# 05__eda__esp32_-__2024-09-18.net
KiCad netlist of a schematic drawn in EasyEDA Pro
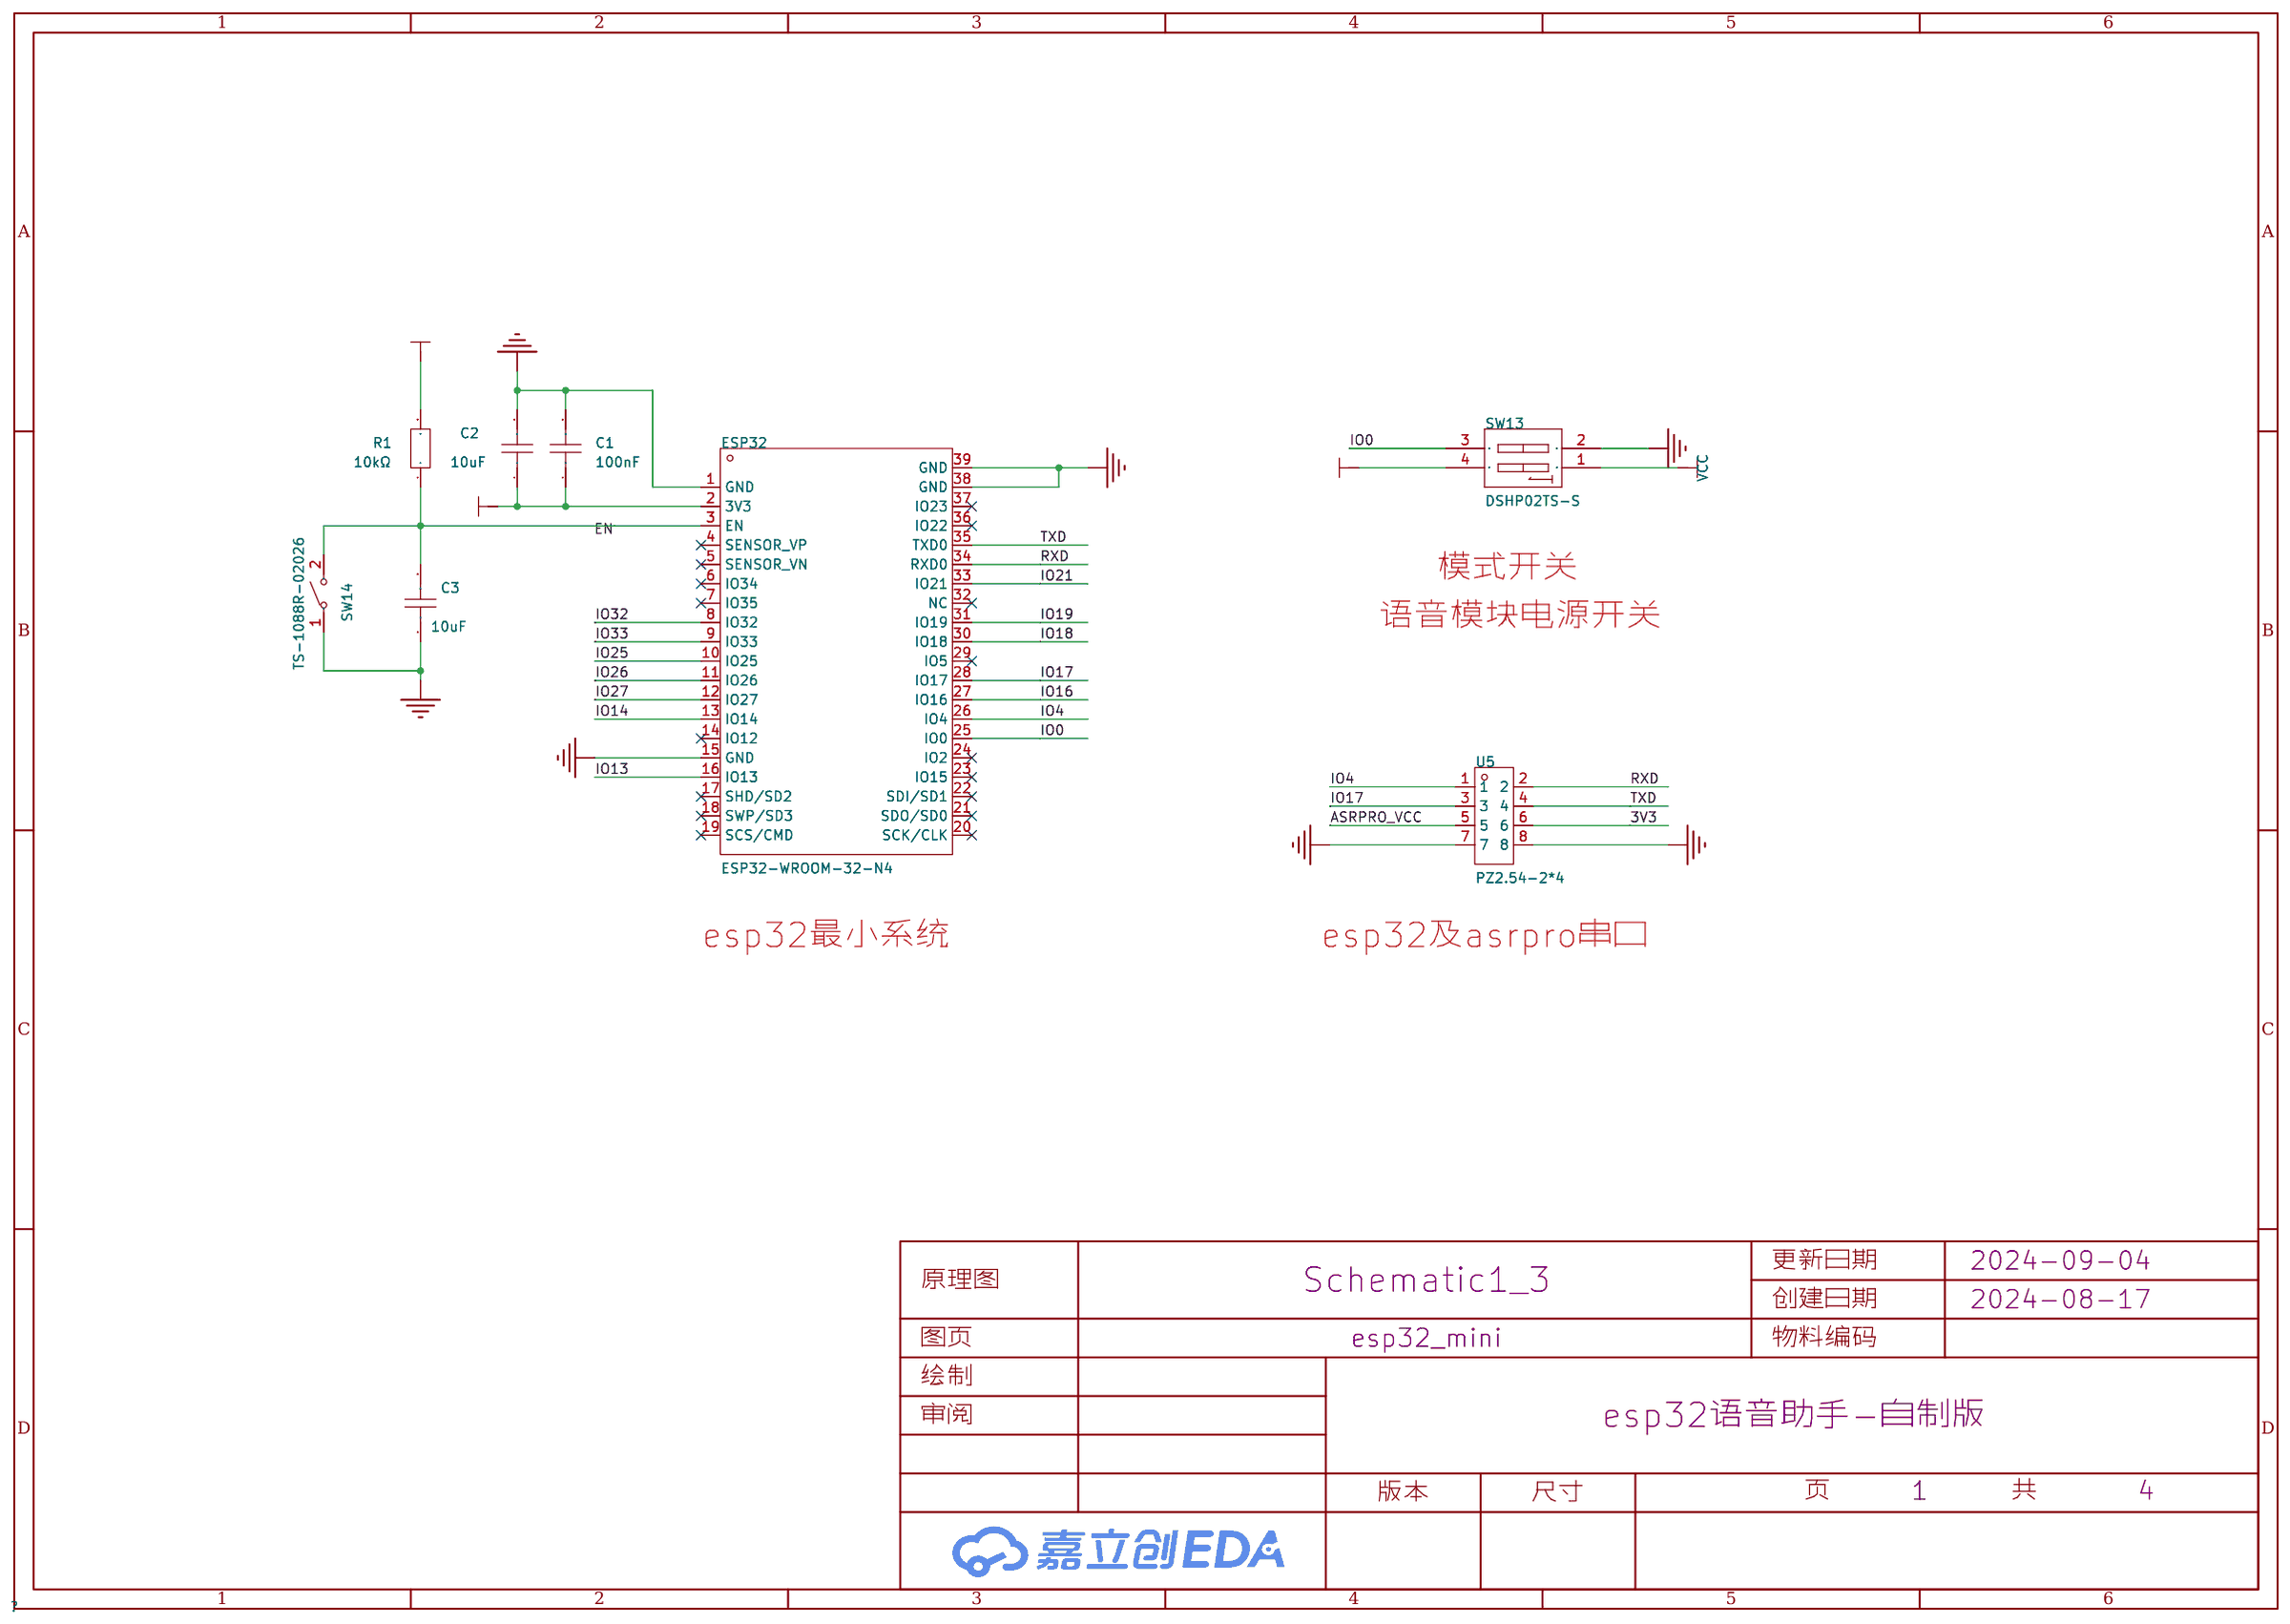
[diagram p0: esp32_mini]
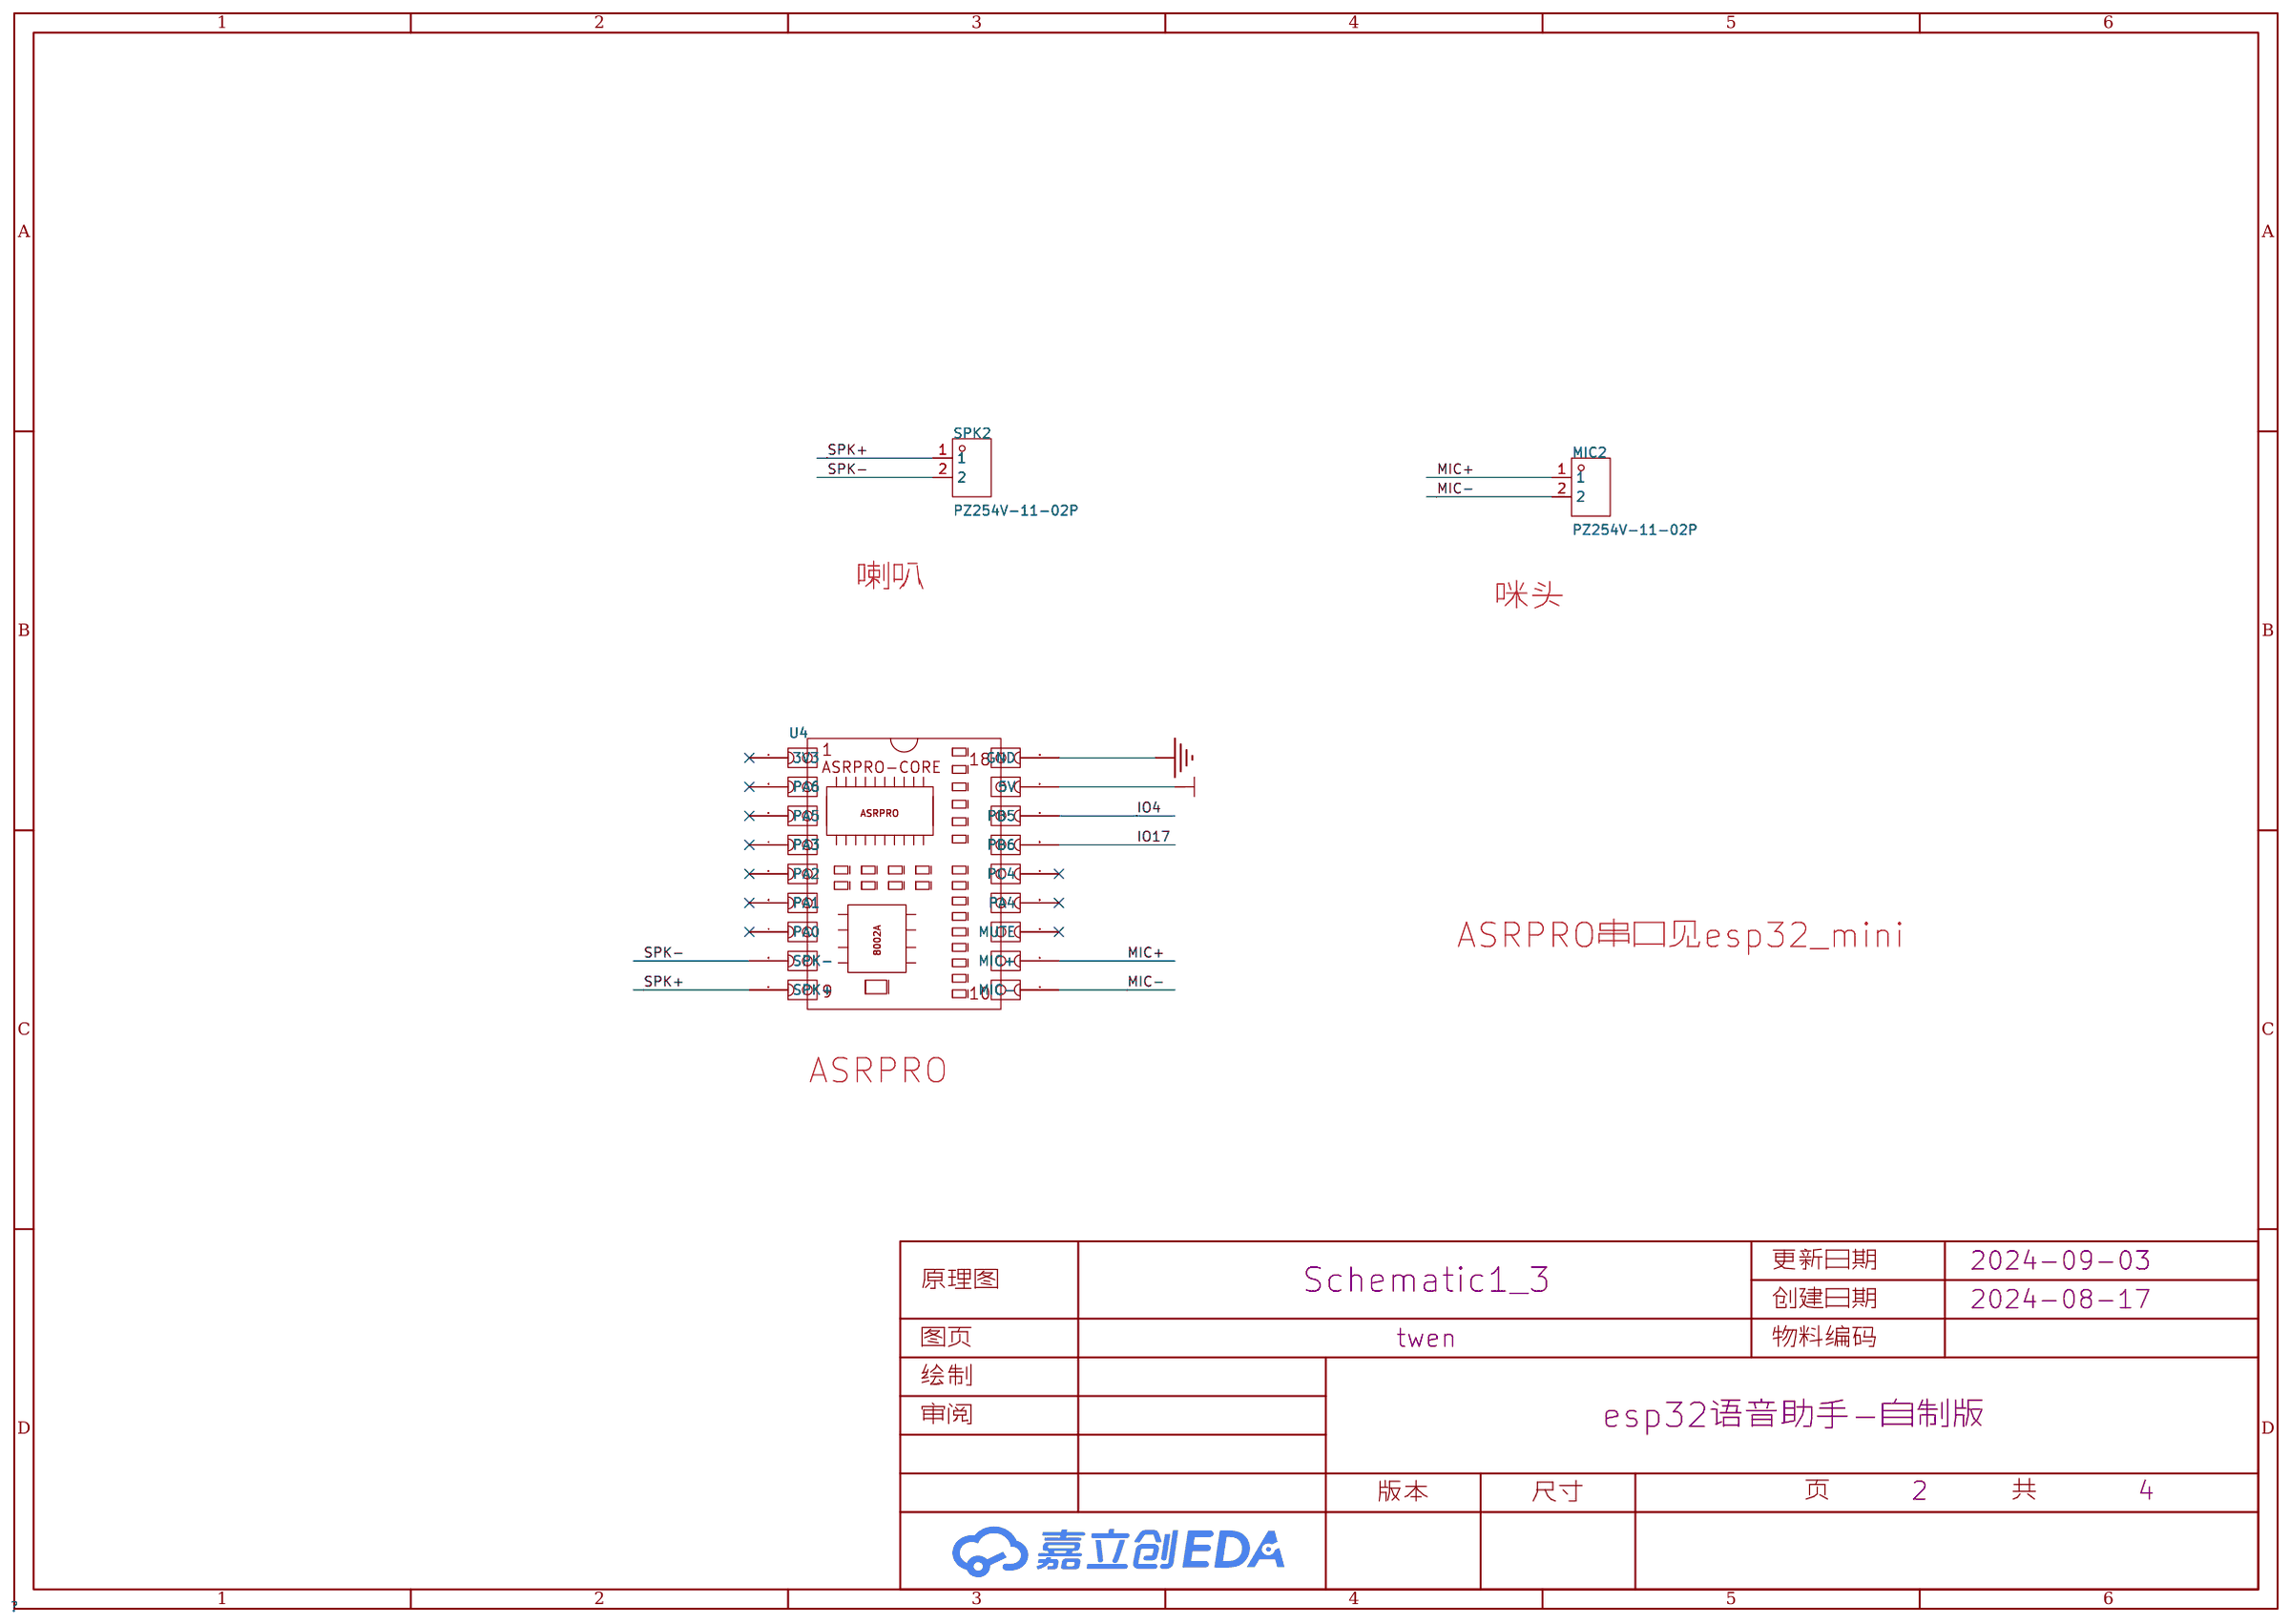
[diagram p1: twen]
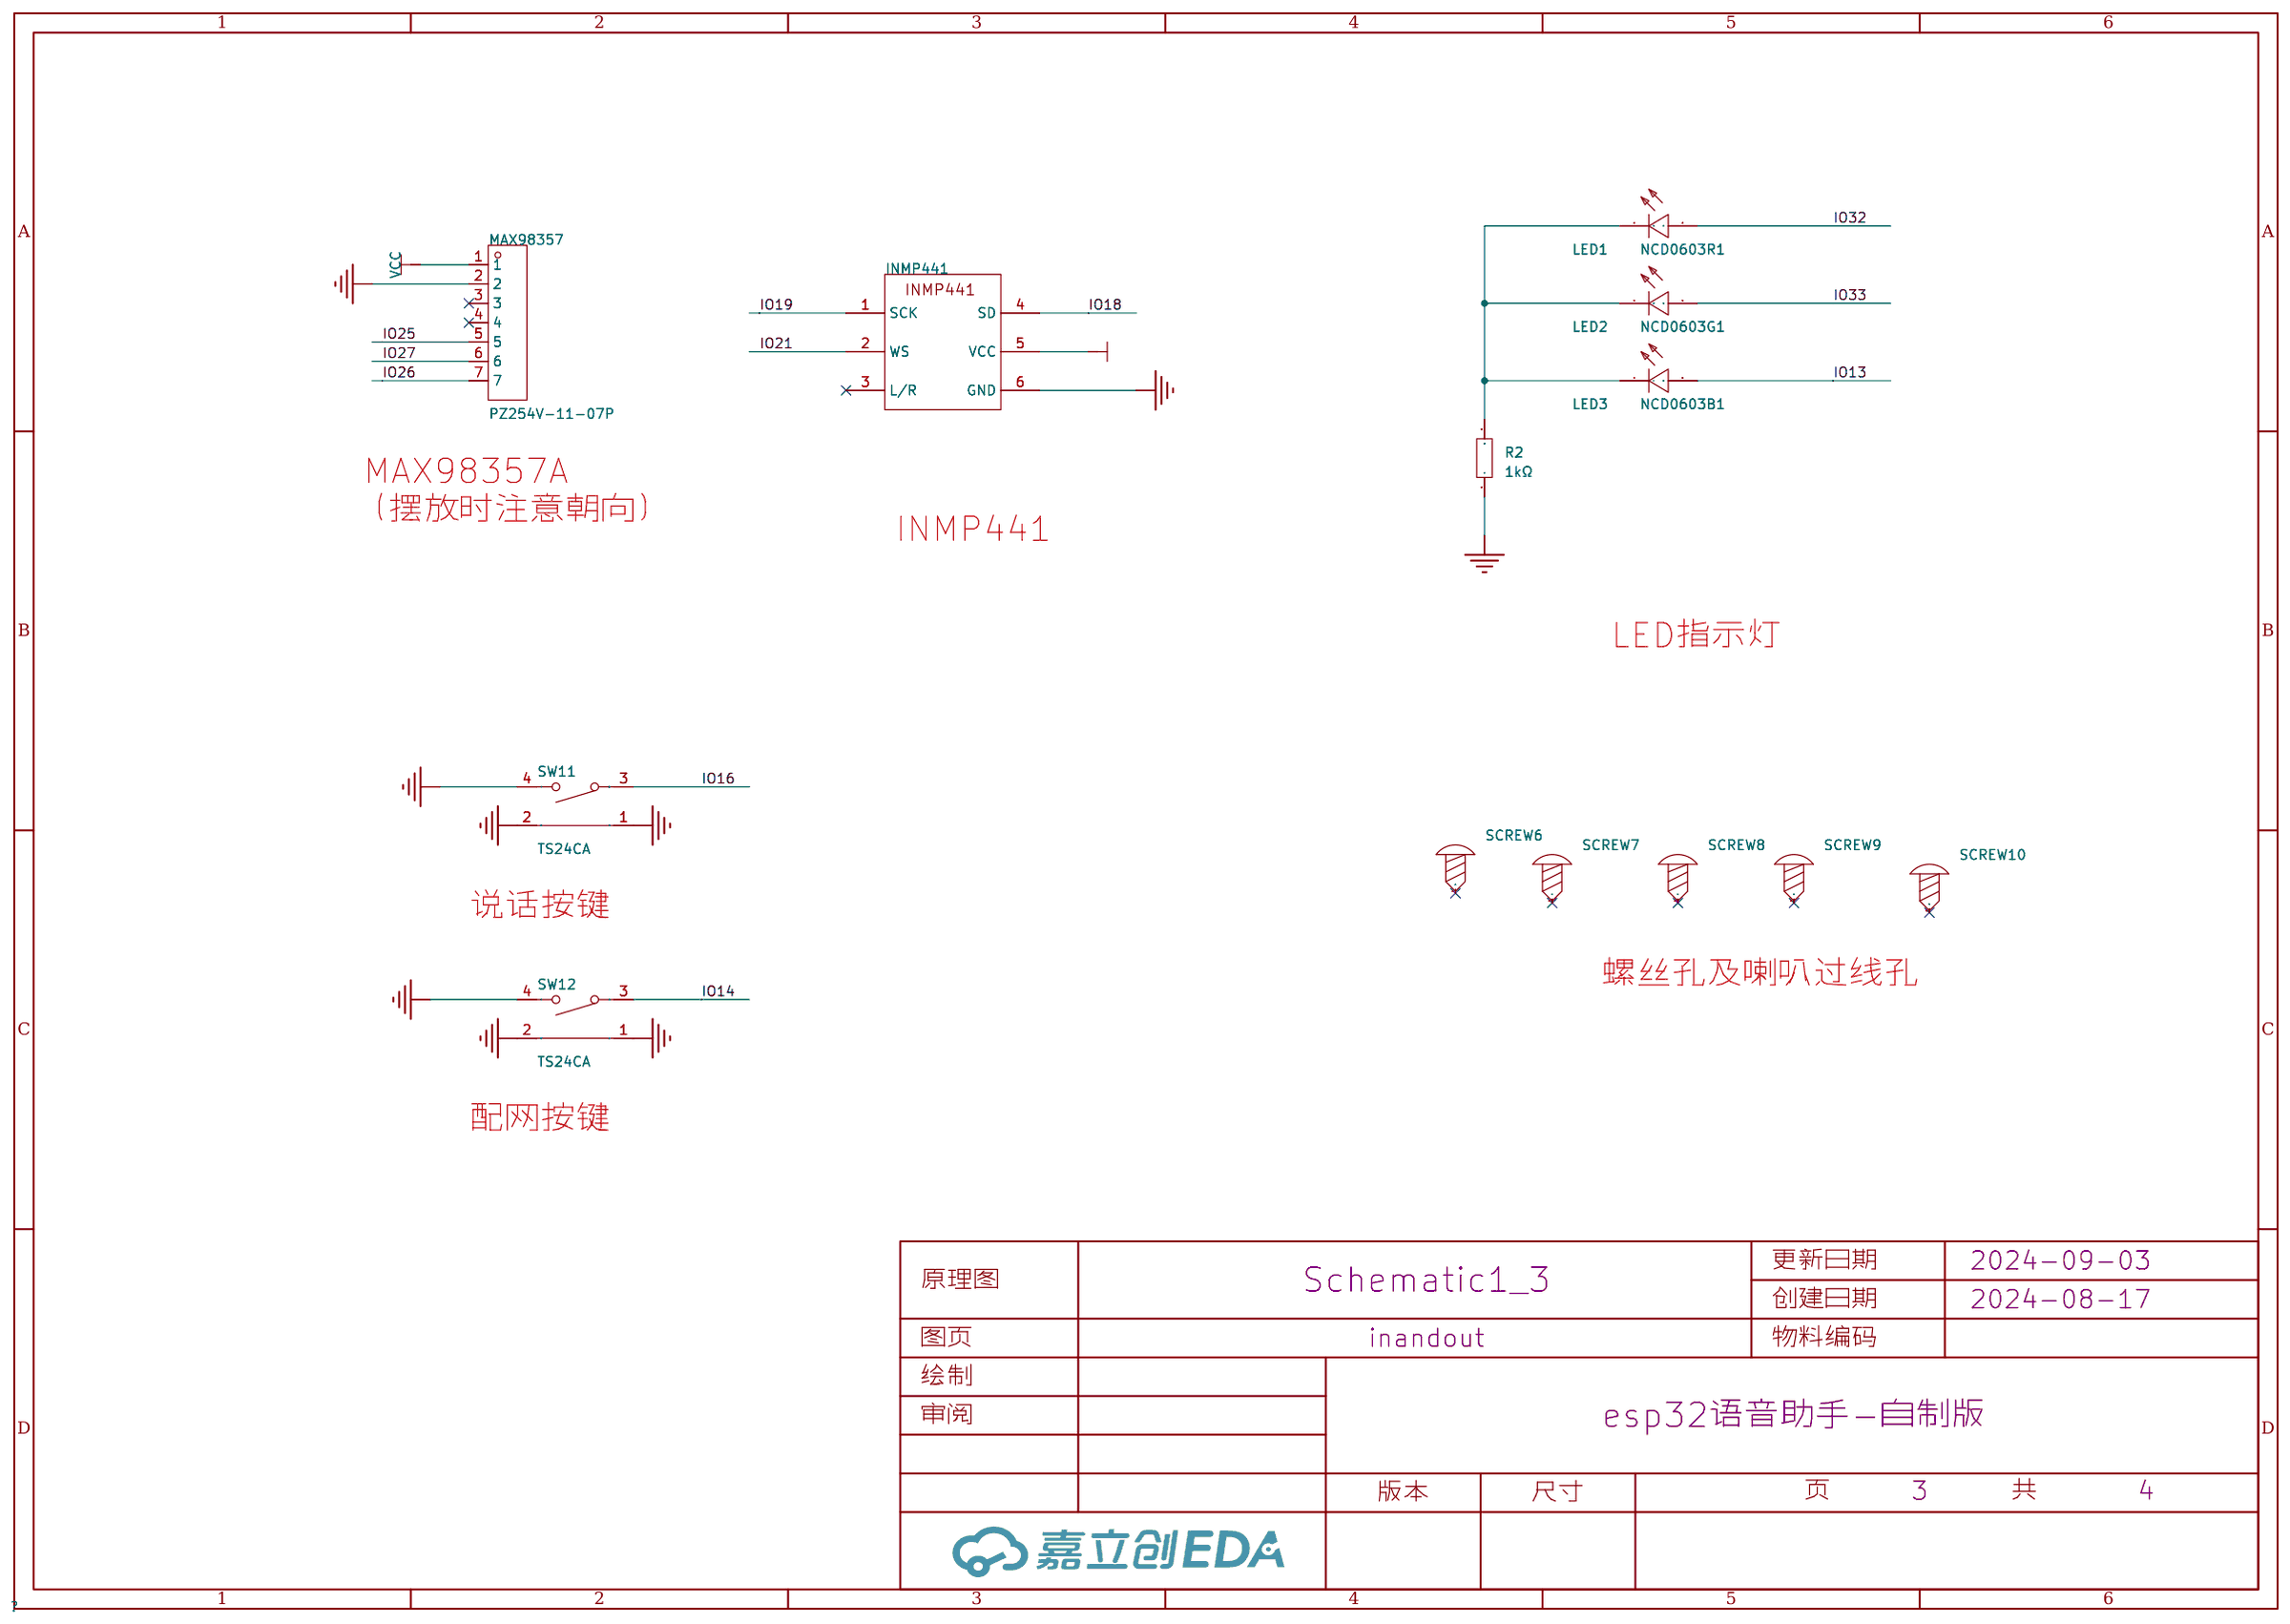
[diagram p2: inandout]
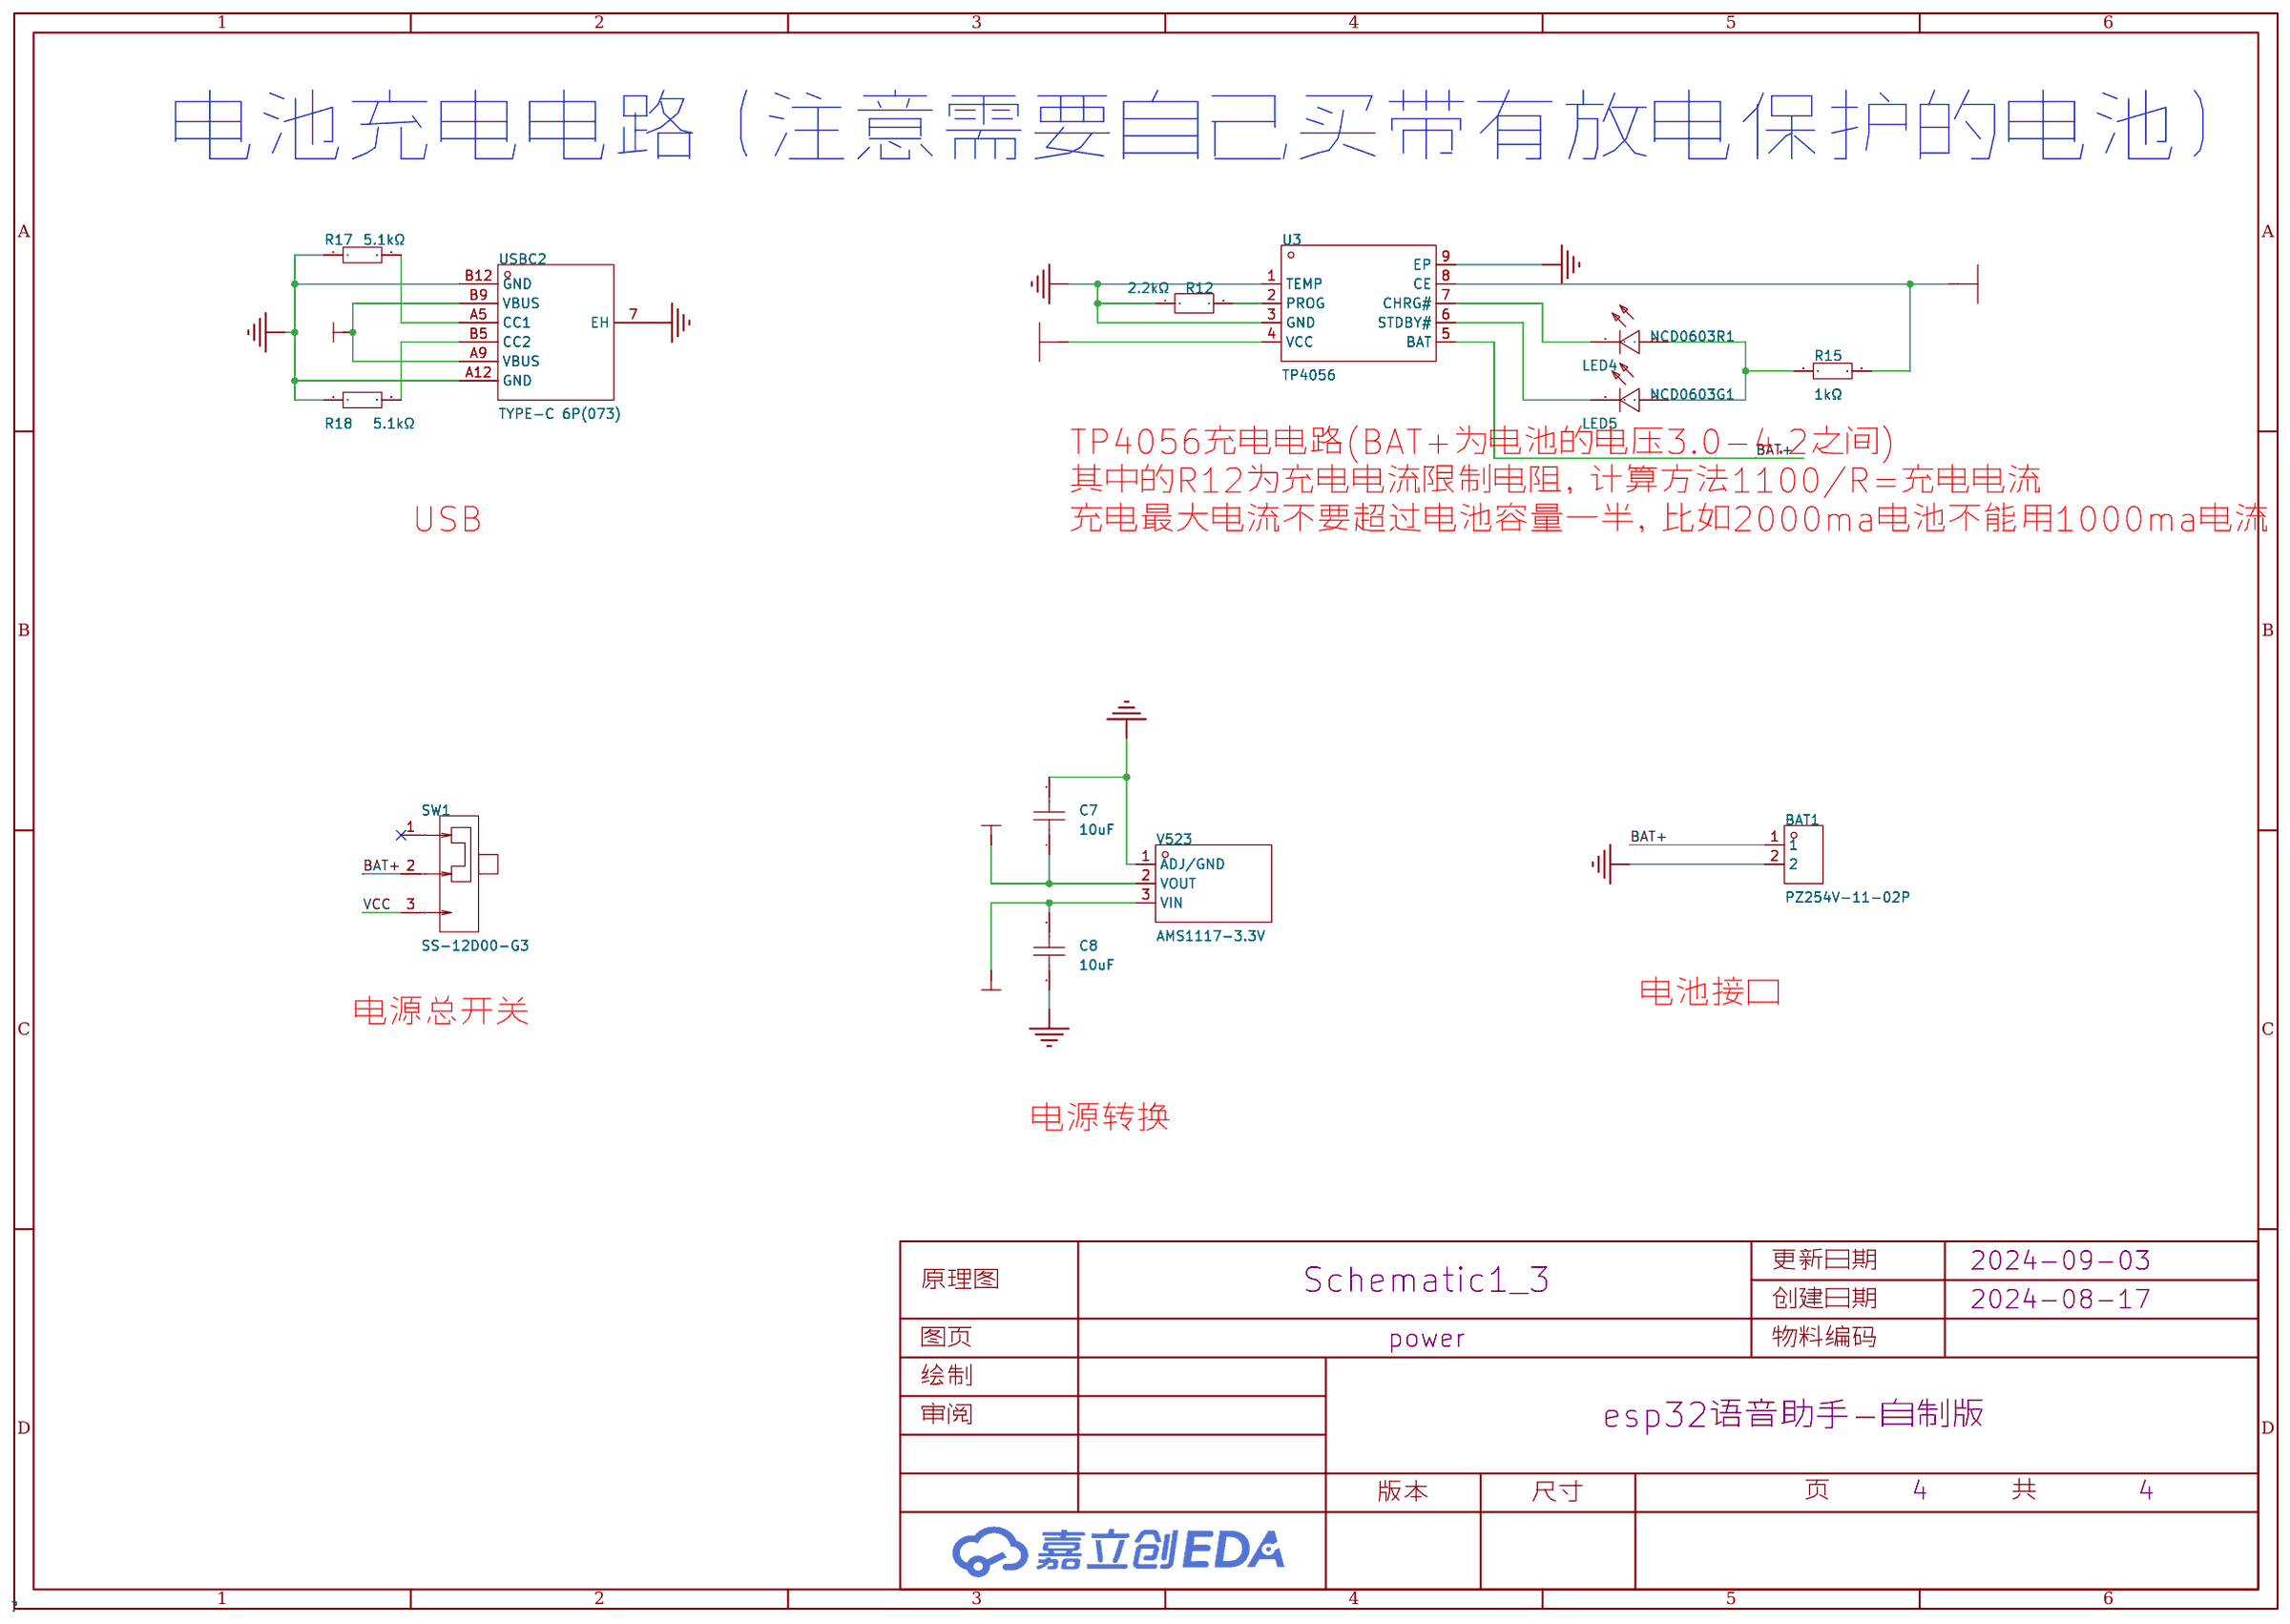
[diagram p3: power]

(export (version "E")
  (design (tool "Eeschema 10.0.6"))
  (components
    (comp (ref "C1")
      (value "100nF")
      (footprint "easyedapro:C0603")
      (description "容值:100nF;精度:±10%;额定电压:50V;材质(温度系数):X7R;")
      (fields
        (field (name "Manufacturer Part") "CC0603KRX7R9BB104")
        (field (name "Manufacturer") "YAGEO(国巨)")
      )
      (libsource (lib "easyedapro") (part "CC0603KRX7R9BB104"))
    )
    (comp (ref "C2")
      (value "10uF")
      (footprint "easyedapro:C0603")
      (description "容值:10uF;精度:±20%;额定电压:25V;材质(温度系数):X5R;")
      (fields
        (field (name "Manufacturer Part") "CL10A106MA8NRNC")
        (field (name "Manufacturer") "SAMSUNG(三星)")
      )
      (libsource (lib "easyedapro") (part "CL10A106MA8NRNC"))
    )
    (comp (ref "C3")
      (value "10uF")
      (footprint "easyedapro:C0603")
      (description "容值:10uF;精度:±20%;额定电压:25V;材质(温度系数):X5R;")
      (fields
        (field (name "Manufacturer Part") "CL10A106MA8NRNC")
        (field (name "Manufacturer") "SAMSUNG(三星)")
      )
      (libsource (lib "easyedapro") (part "CL10A106MA8NRNC"))
    )
    (comp (ref "ESP32")
      (value "ESP32-WROOM-32-N4")
      (footprint "easyedapro:WIFIM-SMD_ESP32-WROOM-32-N4")
      (description "WiFi+蓝牙4.2+双核CPU,ESP32")
      (fields (field (name "Manufacturer") "ESPRESSIF(乐鑫)"))
      (libsource (lib "easyedapro") (part "ESP32-WROOM-32"))
    )
    (comp (ref "R1")
      (value "10kΩ")
      (footprint "easyedapro:R0603")
      (description "电阻类型:厚膜电阻;阻值:10kΩ;精度:±5%;功率:100mW;最大工作电压:75V;温度系数:±100ppm/°C;")
      (fields (field (name "Manufacturer Part") "FRC0603J103TS") (field (name "Manufacturer") "FOJAN(富捷)"))
      (libsource (lib "easyedapro") (part "FRC0603J103TS"))
    )
    (comp (ref "SW13")
      (value "DSHP02TS-S")
      (footprint "easyedapro:SW-SMD_DSHP02TS-S_1")
      (description "类型:平拨,凹槽式;电路结构:单刀单掷;开关位数:2位;额定电流:25mA;额定电压:24V;使用寿命:3千次;颜色:黑色;")
      (fields (field (name "Manufacturer") "XKB Connectivity(中国星坤)"))
      (libsource (lib "easyedapro") (part "DSHP02TS-S"))
    )
    (comp (ref "SW14")
      (value "TS-1088R-02026")
      (footprint "easyedapro:SW-SMD_L3.9-W3.0-P4.45")
      (description "电路结构:单刀单掷;按钮形状:圆形按钮;安装方式:立贴;开关长度:3.9mm;开关宽度:2.93mm;开关高度:2mm;触点电流:50mA;额定电压(DC):12V;带灯:-;机械寿命:-;")
      (fields (field (name "Manufacturer") "XUNPU(讯普)"))
      (libsource (lib "easyedapro") (part "TS-1088R-02026"))
    )
    (comp (ref "U5")
      (value "PZ2.54-2*4")
      (footprint "easyedapro:HDR-TH_8P-P2.54-V-M-R2-C4-S2.54")
      (description "插针结构:2x4P;间距:2.54mm;排数:双排;总PIN位数:8P;")
      (fields (field (name "Manufacturer") "ZHOURI(洲日)"))
      (libsource (lib "easyedapro") (part "PZ2.54-2*4"))
    )
    (comp (ref "MIC2")
      (value "PZ254V-11-02P")
      (footprint "easyedapro:HDR-TH_2P-P2.54-V-M")
      (fields (field (name "Manufacturer") "XFCN(兴飞)"))
      (libsource (lib "easyedapro") (part "PZ254V-11-02P"))
    )
    (comp (ref "SPK2")
      (value "PZ254V-11-02P")
      (footprint "easyedapro:HDR-TH_2P-P2.54-V-M")
      (fields (field (name "Manufacturer") "XFCN(兴飞)"))
      (libsource (lib "easyedapro") (part "PZ254V-11-02P"))
    )
    (comp (ref "U4")
      (value "~")
      (footprint "easyedapro:ASRPRO-CORE-1")
      (libsource (lib "easyedapro") (part "ASRPRO-CORE 核心板1"))
    )
    (comp (ref "INMP441")
      (value "~")
      (footprint "easyedapro:INMP441")
      (libsource (lib "easyedapro") (part "inmp441_数字麦克风"))
    )
    (comp (ref "LED1")
      (value "NCD0603R1")
      (footprint "easyedapro:LED0603-RD_RED")
      (fields (field (name "Manufacturer") "国星光电"))
      (libsource (lib "easyedapro") (part "FC-DA1608HRK-620D"))
    )
    (comp (ref "LED2")
      (value "NCD0603G1")
      (footprint "easyedapro:LED0603-RD")
      (fields (field (name "Manufacturer") "国星光电"))
      (libsource (lib "easyedapro") (part "FC-D1608UGK-520D10"))
    )
    (comp (ref "LED3")
      (value "NCD0603B1")
      (footprint "easyedapro:LED0603-RD")
      (fields (field (name "Manufacturer") "国星光电"))
      (libsource (lib "easyedapro") (part "FC-DA1608BK-470H10"))
    )
    (comp (ref "MAX98357")
      (value "PZ254V-11-07P")
      (footprint "easyedapro:HDR-TH_7P-P2.54-V-M")
      (fields (field (name "Manufacturer") "XFCN(兴飞)"))
      (libsource (lib "easyedapro") (part "PZ254V-11-07P"))
    )
    (comp (ref "R2")
      (value "1kΩ")
      (footprint "easyedapro:R0603")
      (description "电阻类型:厚膜电阻;阻值:1kΩ;精度:±1%;功率:100mW;最大工作电压:75V;温度系数:±100ppm/°C;")
      (fields (field (name "Manufacturer Part") "RC0603FR-071KL") (field (name "Manufacturer") "YAGEO(国巨)"))
      (libsource (lib "easyedapro") (part "RC0603FR-071KL"))
    )
    (comp (ref "SCREW6")
      (value "~")
      (footprint "easyedapro:M2螺丝")
      (libsource (lib "easyedapro") (part "螺丝孔"))
    )
    (comp (ref "SCREW7")
      (value "~")
      (footprint "easyedapro:M2螺丝")
      (libsource (lib "easyedapro") (part "螺丝孔"))
    )
    (comp (ref "SCREW8")
      (value "~")
      (footprint "easyedapro:M2螺丝")
      (libsource (lib "easyedapro") (part "螺丝孔"))
    )
    (comp (ref "SCREW9")
      (value "~")
      (footprint "easyedapro:M2螺丝")
      (libsource (lib "easyedapro") (part "螺丝孔"))
    )
    (comp (ref "SCREW10")
      (value "~")
      (footprint "easyedapro:M2螺丝")
      (libsource (lib "easyedapro") (part "螺丝孔"))
    )
    (comp (ref "SW11")
      (value "TS24CA")
      (footprint "easyedapro:SW-SMD_TS24CA")
      (description "电路结构:单刀单掷;按钮形状:矩形按钮;安装方式:卧贴;开关长度:4.55mm;开关宽度:1.8mm;开关高度:3.5mm;触点电流:50mA;额定电压(DC):12V;带灯:-;机械寿命:-;")
      (fields (field (name "Manufacturer") "SHOU HAN(首韩)"))
      (libsource (lib "easyedapro") (part "TS24CA"))
    )
    (comp (ref "SW12")
      (value "TS24CA")
      (footprint "easyedapro:SW-SMD_TS24CA")
      (description "电路结构:单刀单掷;按钮形状:矩形按钮;安装方式:卧贴;开关长度:4.55mm;开关宽度:1.8mm;开关高度:3.5mm;触点电流:50mA;额定电压(DC):12V;带灯:-;机械寿命:-;")
      (fields (field (name "Manufacturer") "SHOU HAN(首韩)"))
      (libsource (lib "easyedapro") (part "TS24CA"))
    )
    (comp (ref "BAT1")
      (value "PZ254V-11-02P")
      (footprint "easyedapro:HDR-TH_2P-P2.54-V-M")
      (fields (field (name "Manufacturer") "XFCN(兴飞)"))
      (libsource (lib "easyedapro") (part "PZ254V-11-02P"))
    )
    (comp (ref "C7")
      (value "10uF")
      (footprint "easyedapro:C0603")
      (description "容值:10uF;精度:±10%;额定电压:10V;材质(温度系数):X5R;")
      (fields
        (field (name "Manufacturer Part") "CL10A106KP8NNNC")
        (field (name "Manufacturer") "SAMSUNG(三星)")
      )
      (libsource (lib "easyedapro") (part "CL10A106KP8NNNC"))
    )
    (comp (ref "C8")
      (value "10uF")
      (footprint "easyedapro:C0603")
      (description "容值:10uF;精度:±10%;额定电压:10V;材质(温度系数):X5R;")
      (fields
        (field (name "Manufacturer Part") "CL10A106KP8NNNC")
        (field (name "Manufacturer") "SAMSUNG(三星)")
      )
      (libsource (lib "easyedapro") (part "CL10A106KP8NNNC"))
    )
    (comp (ref "LED4")
      (value "NCD0603R1")
      (footprint "easyedapro:LED0603-RD_RED")
      (fields (field (name "Manufacturer") "国星光电"))
      (libsource (lib "easyedapro") (part "FC-DA1608HRK-620D"))
    )
    (comp (ref "LED5")
      (value "NCD0603G1")
      (footprint "easyedapro:LED0603-RD")
      (fields (field (name "Manufacturer") "国星光电"))
      (libsource (lib "easyedapro") (part "FC-D1608UGK-520D10"))
    )
    (comp (ref "R12")
      (value "2.2kΩ")
      (footprint "easyedapro:R0603")
      (description "电阻类型:厚膜电阻;阻值:2.2kΩ;精度:±5%;功率:100mW;最大工作电压:75V;温度系数:±100ppm/°C;")
      (fields (field (name "Manufacturer Part") "FRC0603J222 TS") (field (name "Manufacturer") "FOJAN(富捷)"))
      (libsource (lib "easyedapro") (part "FRC0603J222 TS"))
    )
    (comp (ref "R15")
      (value "1kΩ")
      (footprint "easyedapro:R0603")
      (description "电阻类型:厚膜电阻;阻值:1kΩ;精度:±1%;功率:100mW;最大工作电压:75V;温度系数:±100ppm/°C;")
      (fields (field (name "Manufacturer Part") "RC0603FR-071KL") (field (name "Manufacturer") "YAGEO(国巨)"))
      (libsource (lib "easyedapro") (part "RC0603FR-071KL"))
    )
    (comp (ref "R17")
      (value "5.1kΩ")
      (footprint "easyedapro:R0603")
      (description "电阻类型:厚膜电阻;阻值:5.1kΩ;精度:±1%;功率:100mW;最大工作电压:75V;温度系数:±100ppm/°C;")
      (fields
        (field (name "Manufacturer Part") "0603WAF5101T5E")
        (field (name "Manufacturer") "UNI-ROYAL(厚声)")
      )
      (libsource (lib "easyedapro") (part "0603WAF5101T5E"))
    )
    (comp (ref "R18")
      (value "5.1kΩ")
      (footprint "easyedapro:R0603")
      (description "电阻类型:厚膜电阻;阻值:5.1kΩ;精度:±1%;功率:100mW;最大工作电压:75V;温度系数:±100ppm/°C;")
      (fields
        (field (name "Manufacturer Part") "0603WAF5101T5E")
        (field (name "Manufacturer") "UNI-ROYAL(厚声)")
      )
      (libsource (lib "easyedapro") (part "0603WAF5101T5E"))
    )
    (comp (ref "SW1")
      (value "SS-12D00-G3")
      (footprint "easyedapro:SW-TH_SS-12D00-G3")
      (fields (field (name "Manufacturer") "SOFNG(硕方)"))
      (libsource (lib "easyedapro") (part "SS-12D00-G3"))
    )
    (comp (ref "U3")
      (value "TP4056")
      (footprint "easyedapro:ESOP-8_L4.9-W3.9-P1.27-LS6.0-BL-EP")
      (fields (field (name "Manufacturer") "UMW(友台半导体)"))
      (libsource (lib "easyedapro") (part "TP4056_C725790"))
    )
    (comp (ref "USBC2")
      (value "TYPE-C 6P(073)")
      (footprint "easyedapro:TYPE-C-SMD_TYPE-C-6P_5")
      (description "连接器类型:Type-C;标准:-;公母:母;端口数量:1;触点数量:6P;安装方式:卧贴;额定电流 - 电源:5A;工作温度范围:-25°C~+85°C;")
      (fields (field (name "Manufacturer") "SHOU HAN(首韩)"))
      (libsource (lib "easyedapro") (part "TYPE-C 6P(073)"))
    )
    (comp (ref "V523")
      (value "AMS1117-3.3V")
      (footprint "easyedapro:SOT-89-3_L4.5-W2.5-P1.50-LS4.2-BR")
      (description "输出类型:固定;最大输入电压:18V;输出电压:3.3V;最大输出电流:1A;输出极性:正极;")
      (fields (field (name "Manufacturer") "MSKSEMI(美森科)"))
      (libsource (lib "easyedapro") (part "AMS1117-3.3V_C5120796"))
    )
  )
  (nets
    (net (code "1") (name "3V3") (class "Default")
      (node (ref "C1") (pin "1") (pinfunction "1_1") (pintype "unspecified"))
      (node (ref "C2") (pin "1") (pinfunction "1_1") (pintype "unspecified"))
      (node (ref "C7") (pin "1") (pinfunction "1_1") (pintype "unspecified"))
      (node (ref "ESP32") (pin "2") (pinfunction "3V3_2") (pintype "unspecified"))
      (node (ref "INMP441") (pin "5") (pinfunction "VCC_5") (pintype "unspecified"))
      (node (ref "R1") (pin "2") (pinfunction "2_2") (pintype "unspecified"))
      (node (ref "U5") (pin "6") (pinfunction "6_6") (pintype "unspecified"))
      (node (ref "V523") (pin "2") (pinfunction "VOUT_2") (pintype "unspecified"))
    )
    (net (code "2") (name "5VIN") (class "Default")
      (node (ref "R15") (pin "1") (pinfunction "1_1") (pintype "input"))
      (node (ref "U3") (pin "4") (pinfunction "VCC_4") (pintype "unspecified"))
      (node (ref "U3") (pin "8") (pinfunction "CE_8") (pintype "unspecified"))
      (node (ref "USBC2") (pin "A9") (pinfunction "VBUS_A9") (pintype "unspecified"))
      (node (ref "USBC2") (pin "B9") (pinfunction "VBUS_B9") (pintype "unspecified"))
    )
    (net (code "3") (name "ASRPRO_VCC") (class "Default")
      (node (ref "SW13") (pin "4") (pinfunction "B1_4") (pintype "input"))
      (node (ref "U4") (pin "17") (pinfunction "5V_17") (pintype "unspecified"))
      (node (ref "U5") (pin "5") (pinfunction "5_5") (pintype "unspecified"))
    )
    (net (code "4") (name "BAT+") (class "Default")
      (node (ref "BAT1") (pin "1") (pinfunction "1_1") (pintype "unspecified"))
      (node (ref "SW1") (pin "2") (pinfunction "2_2") (pintype "unspecified"))
      (node (ref "U3") (pin "5") (pinfunction "BAT_5") (pintype "unspecified"))
    )
    (net (code "5") (name "EN") (class "Default")
      (node (ref "C3") (pin "2") (pinfunction "2_2") (pintype "unspecified"))
      (node (ref "ESP32") (pin "3") (pinfunction "EN_3") (pintype "unspecified"))
      (node (ref "R1") (pin "1") (pinfunction "1_1") (pintype "unspecified"))
      (node (ref "SW14") (pin "2") (pinfunction "2_2") (pintype "unspecified"))
    )
    (net (code "6") (name "GND") (class "Default")
      (node (ref "BAT1") (pin "2") (pinfunction "2_2") (pintype "unspecified"))
      (node (ref "C1") (pin "2") (pinfunction "2_2") (pintype "unspecified"))
      (node (ref "C2") (pin "2") (pinfunction "2_2") (pintype "unspecified"))
      (node (ref "C3") (pin "1") (pinfunction "1_1") (pintype "unspecified"))
      (node (ref "C7") (pin "2") (pinfunction "2_2") (pintype "unspecified"))
      (node (ref "C8") (pin "1") (pinfunction "1_1") (pintype "unspecified"))
      (node (ref "ESP32") (pin "1") (pinfunction "GND_1") (pintype "unspecified"))
      (node (ref "ESP32") (pin "15") (pinfunction "GND_15") (pintype "unspecified"))
      (node (ref "ESP32") (pin "38") (pinfunction "GND_38") (pintype "unspecified"))
      (node (ref "ESP32") (pin "39") (pinfunction "GND_39") (pintype "unspecified"))
      (node (ref "INMP441") (pin "6") (pinfunction "GND_6") (pintype "unspecified"))
      (node (ref "MAX98357") (pin "2") (pinfunction "2_2") (pintype "unspecified"))
      (node (ref "R12") (pin "1") (pinfunction "1_1") (pintype "unspecified"))
      (node (ref "R17") (pin "1") (pinfunction "1_1") (pintype "input"))
      (node (ref "R18") (pin "1") (pinfunction "1_1") (pintype "input"))
      (node (ref "R2") (pin "1") (pinfunction "1_1") (pintype "input"))
      (node (ref "SW11") (pin "1") (pinfunction "1_1") (pintype "input"))
      (node (ref "SW11") (pin "2") (pinfunction "2_2") (pintype "input"))
      (node (ref "SW11") (pin "4") (pinfunction "4_4") (pintype "input"))
      (node (ref "SW12") (pin "1") (pinfunction "1_1") (pintype "input"))
      (node (ref "SW12") (pin "2") (pinfunction "2_2") (pintype "input"))
      (node (ref "SW12") (pin "4") (pinfunction "4_4") (pintype "input"))
      (node (ref "SW13") (pin "2") (pinfunction "A2_2") (pintype "input"))
      (node (ref "SW14") (pin "1") (pinfunction "1_1") (pintype "unspecified"))
      (node (ref "U3") (pin "1") (pinfunction "TEMP_1") (pintype "unspecified"))
      (node (ref "U3") (pin "3") (pinfunction "GND_3") (pintype "unspecified"))
      (node (ref "U3") (pin "9") (pinfunction "EP_9") (pintype "unspecified"))
      (node (ref "U4") (pin "18") (pinfunction "GND_18") (pintype "unspecified"))
      (node (ref "U5") (pin "7") (pinfunction "7_7") (pintype "unspecified"))
      (node (ref "U5") (pin "8") (pinfunction "8_8") (pintype "unspecified"))
      (node (ref "USBC2") (pin "7") (pinfunction "EH_7") (pintype "unspecified"))
      (node (ref "USBC2") (pin "A12") (pinfunction "GND_A12") (pintype "unspecified"))
      (node (ref "USBC2") (pin "B12") (pinfunction "GND_B12") (pintype "unspecified"))
      (node (ref "V523") (pin "1") (pinfunction "ADJ/GND_1") (pintype "unspecified"))
    )
    (net (code "7") (name "IO0") (class "Default")
      (node (ref "ESP32") (pin "25") (pinfunction "IO0_25") (pintype "unspecified"))
      (node (ref "SW13") (pin "3") (pinfunction "B2_3") (pintype "input"))
    )
    (net (code "8") (name "IO4") (class "Default")
      (node (ref "ESP32") (pin "26") (pinfunction "IO4_26") (pintype "unspecified"))
      (node (ref "U4") (pin "16") (pinfunction "PB5_16") (pintype "unspecified"))
      (node (ref "U5") (pin "1") (pinfunction "1_1") (pintype "unspecified"))
    )
    (net (code "9") (name "IO13") (class "Default")
      (node (ref "ESP32") (pin "16") (pinfunction "IO13_16") (pintype "unspecified"))
      (node (ref "LED3") (pin "2") (pinfunction "+_2") (pintype "input"))
    )
    (net (code "10") (name "IO14") (class "Default")
      (node (ref "ESP32") (pin "13") (pinfunction "IO14_13") (pintype "unspecified"))
      (node (ref "SW12") (pin "3") (pinfunction "3_3") (pintype "input"))
    )
    (net (code "11") (name "IO16") (class "Default")
      (node (ref "ESP32") (pin "27") (pinfunction "IO16_27") (pintype "unspecified"))
      (node (ref "SW11") (pin "3") (pinfunction "3_3") (pintype "input"))
    )
    (net (code "12") (name "IO17") (class "Default")
      (node (ref "ESP32") (pin "28") (pinfunction "IO17_28") (pintype "unspecified"))
      (node (ref "U4") (pin "15") (pinfunction "PB6_15") (pintype "unspecified"))
      (node (ref "U5") (pin "3") (pinfunction "3_3") (pintype "unspecified"))
    )
    (net (code "13") (name "IO18") (class "Default")
      (node (ref "ESP32") (pin "30") (pinfunction "IO18_30") (pintype "unspecified"))
      (node (ref "INMP441") (pin "4") (pinfunction "SD_4") (pintype "unspecified"))
    )
    (net (code "14") (name "IO19") (class "Default")
      (node (ref "ESP32") (pin "31") (pinfunction "IO19_31") (pintype "unspecified"))
      (node (ref "INMP441") (pin "1") (pinfunction "SCK_1") (pintype "unspecified"))
    )
    (net (code "15") (name "IO21") (class "Default")
      (node (ref "ESP32") (pin "33") (pinfunction "IO21_33") (pintype "unspecified"))
      (node (ref "INMP441") (pin "2") (pinfunction "WS_2") (pintype "unspecified"))
    )
    (net (code "16") (name "IO25") (class "Default")
      (node (ref "ESP32") (pin "10") (pinfunction "IO25_10") (pintype "unspecified"))
      (node (ref "MAX98357") (pin "5") (pinfunction "5_5") (pintype "unspecified"))
    )
    (net (code "17") (name "IO26") (class "Default")
      (node (ref "ESP32") (pin "11") (pinfunction "IO26_11") (pintype "unspecified"))
      (node (ref "MAX98357") (pin "7") (pinfunction "7_7") (pintype "unspecified"))
    )
    (net (code "18") (name "IO27") (class "Default")
      (node (ref "ESP32") (pin "12") (pinfunction "IO27_12") (pintype "unspecified"))
      (node (ref "MAX98357") (pin "6") (pinfunction "6_6") (pintype "unspecified"))
    )
    (net (code "19") (name "IO32") (class "Default")
      (node (ref "ESP32") (pin "8") (pinfunction "IO32_8") (pintype "unspecified"))
      (node (ref "LED1") (pin "2") (pinfunction "A_2") (pintype "input"))
    )
    (net (code "20") (name "IO33") (class "Default")
      (node (ref "ESP32") (pin "9") (pinfunction "IO33_9") (pintype "unspecified"))
      (node (ref "LED2") (pin "2") (pinfunction "A_2") (pintype "input"))
    )
    (net (code "21") (name "MIC+") (class "Default")
      (node (ref "MIC2") (pin "1") (pinfunction "1_1") (pintype "unspecified"))
      (node (ref "U4") (pin "11") (pinfunction "MIC+_11") (pintype "unspecified"))
    )
    (net (code "22") (name "MIC-") (class "Default")
      (node (ref "MIC2") (pin "2") (pinfunction "2_2") (pintype "unspecified"))
      (node (ref "U4") (pin "10") (pinfunction "MIC-_10") (pintype "unspecified"))
    )
    (net (code "23") (name "Net-(LED1-K)") (class "Default")
      (node (ref "LED1") (pin "1") (pinfunction "K_1") (pintype "input"))
      (node (ref "LED2") (pin "1") (pinfunction "K_1") (pintype "input"))
      (node (ref "LED3") (pin "1") (pinfunction "-_1") (pintype "input"))
      (node (ref "R2") (pin "2") (pinfunction "2_2") (pintype "input"))
    )
    (net (code "24") (name "Net-(LED4-A)") (class "Default")
      (node (ref "LED4") (pin "2") (pinfunction "A_2") (pintype "input"))
      (node (ref "LED5") (pin "2") (pinfunction "A_2") (pintype "input"))
      (node (ref "R15") (pin "2") (pinfunction "2_2") (pintype "input"))
    )
    (net (code "25") (name "Net-(LED4-K)") (class "Default")
      (node (ref "LED4") (pin "1") (pinfunction "K_1") (pintype "input"))
      (node (ref "U3") (pin "7") (pinfunction "CHRG#_7") (pintype "unspecified"))
    )
    (net (code "26") (name "Net-(LED5-K)") (class "Default")
      (node (ref "LED5") (pin "1") (pinfunction "K_1") (pintype "input"))
      (node (ref "U3") (pin "6") (pinfunction "STDBY#_6") (pintype "unspecified"))
    )
    (net (code "27") (name "Net-(U3-PROG)") (class "Default")
      (node (ref "R12") (pin "2") (pinfunction "2_2") (pintype "unspecified"))
      (node (ref "U3") (pin "2") (pinfunction "PROG_2") (pintype "unspecified"))
    )
    (net (code "28") (name "Net-(USBC2-CC1)") (class "Default")
      (node (ref "R17") (pin "2") (pinfunction "2_2") (pintype "input"))
      (node (ref "USBC2") (pin "A5") (pinfunction "CC1_A5") (pintype "unspecified"))
    )
    (net (code "29") (name "Net-(USBC2-CC2)") (class "Default")
      (node (ref "R18") (pin "2") (pinfunction "2_2") (pintype "input"))
      (node (ref "USBC2") (pin "B5") (pinfunction "CC2_B5") (pintype "unspecified"))
    )
    (net (code "30") (name "RXD") (class "Default")
      (node (ref "ESP32") (pin "34") (pinfunction "RXD0_34") (pintype "unspecified"))
      (node (ref "U5") (pin "2") (pinfunction "2_2") (pintype "unspecified"))
    )
    (net (code "31") (name "SPK+") (class "Default")
      (node (ref "SPK2") (pin "1") (pinfunction "1_1") (pintype "unspecified"))
      (node (ref "U4") (pin "9") (pinfunction "SPK+_9") (pintype "unspecified"))
    )
    (net (code "32") (name "SPK-") (class "Default")
      (node (ref "SPK2") (pin "2") (pinfunction "2_2") (pintype "unspecified"))
      (node (ref "U4") (pin "8") (pinfunction "SPK-_8") (pintype "unspecified"))
    )
    (net (code "33") (name "TXD") (class "Default")
      (node (ref "ESP32") (pin "35") (pinfunction "TXD0_35") (pintype "unspecified"))
      (node (ref "U5") (pin "4") (pinfunction "4_4") (pintype "unspecified"))
    )
    (net (code "34") (name "VCC") (class "Default")
      (node (ref "C8") (pin "2") (pinfunction "2_2") (pintype "unspecified"))
      (node (ref "MAX98357") (pin "1") (pinfunction "1_1") (pintype "unspecified"))
      (node (ref "SW1") (pin "3") (pinfunction "3_3") (pintype "unspecified"))
      (node (ref "SW13") (pin "1") (pinfunction "A1_1") (pintype "input"))
      (node (ref "V523") (pin "3") (pinfunction "VIN_3") (pintype "unspecified"))
    )
    (net (code "35") (name "unconnected-(ESP32-IO2-Pad24)") (class "Default")
      (node (ref "ESP32") (pin "24") (pinfunction "IO2_24") (pintype "unspecified+no_connect"))
    )
    (net (code "36") (name "unconnected-(ESP32-IO5-Pad29)") (class "Default")
      (node (ref "ESP32") (pin "29") (pinfunction "IO5_29") (pintype "unspecified+no_connect"))
    )
    (net (code "37") (name "unconnected-(ESP32-IO12-Pad14)") (class "Default")
      (node (ref "ESP32") (pin "14") (pinfunction "IO12_14") (pintype "unspecified+no_connect"))
    )
    (net (code "38") (name "unconnected-(ESP32-IO15-Pad23)") (class "Default")
      (node (ref "ESP32") (pin "23") (pinfunction "IO15_23") (pintype "unspecified+no_connect"))
    )
    (net (code "39") (name "unconnected-(ESP32-IO22-Pad36)") (class "Default")
      (node (ref "ESP32") (pin "36") (pinfunction "IO22_36") (pintype "unspecified+no_connect"))
    )
    (net (code "40") (name "unconnected-(ESP32-IO23-Pad37)") (class "Default")
      (node (ref "ESP32") (pin "37") (pinfunction "IO23_37") (pintype "unspecified+no_connect"))
    )
    (net (code "41") (name "unconnected-(ESP32-IO34-Pad6)") (class "Default")
      (node (ref "ESP32") (pin "6") (pinfunction "IO34_6") (pintype "unspecified+no_connect"))
    )
    (net (code "42") (name "unconnected-(ESP32-IO35-Pad7)") (class "Default")
      (node (ref "ESP32") (pin "7") (pinfunction "IO35_7") (pintype "unspecified+no_connect"))
    )
    (net (code "43") (name "unconnected-(ESP32-NC-Pad32)") (class "Default")
      (node (ref "ESP32") (pin "32") (pinfunction "NC_32") (pintype "unspecified+no_connect"))
    )
    (net (code "44") (name "unconnected-(ESP32-SCK{slash}CLK-Pad20)") (class "Default")
      (node (ref "ESP32") (pin "20") (pinfunction "SCK/CLK_20") (pintype "unspecified+no_connect"))
    )
    (net (code "45") (name "unconnected-(ESP32-SCS{slash}CMD-Pad19)") (class "Default")
      (node (ref "ESP32") (pin "19") (pinfunction "SCS/CMD_19") (pintype "unspecified+no_connect"))
    )
    (net (code "46") (name "unconnected-(ESP32-SDI{slash}SD1-Pad22)") (class "Default")
      (node (ref "ESP32") (pin "22") (pinfunction "SDI/SD1_22") (pintype "unspecified+no_connect"))
    )
    (net (code "47") (name "unconnected-(ESP32-SDO{slash}SD0-Pad21)") (class "Default")
      (node (ref "ESP32") (pin "21") (pinfunction "SDO/SD0_21") (pintype "unspecified+no_connect"))
    )
    (net (code "48") (name "unconnected-(ESP32-SENSOR_VN-Pad5)") (class "Default")
      (node (ref "ESP32") (pin "5") (pinfunction "SENSOR_VN_5") (pintype "unspecified+no_connect"))
    )
    (net (code "49") (name "unconnected-(ESP32-SENSOR_VP-Pad4)") (class "Default")
      (node (ref "ESP32") (pin "4") (pinfunction "SENSOR_VP_4") (pintype "unspecified+no_connect"))
    )
    (net (code "50") (name "unconnected-(ESP32-SHD{slash}SD2-Pad17)") (class "Default")
      (node (ref "ESP32") (pin "17") (pinfunction "SHD/SD2_17") (pintype "unspecified+no_connect"))
    )
    (net (code "51") (name "unconnected-(ESP32-SWP{slash}SD3-Pad18)") (class "Default")
      (node (ref "ESP32") (pin "18") (pinfunction "SWP/SD3_18") (pintype "unspecified+no_connect"))
    )
    (net (code "52") (name "unconnected-(INMP441-L{slash}R-Pad3)") (class "Default")
      (node (ref "INMP441") (pin "3") (pinfunction "L/R_3") (pintype "unspecified+no_connect"))
    )
    (net (code "53") (name "unconnected-(MAX98357-Pad3)") (class "Default")
      (node (ref "MAX98357") (pin "3") (pinfunction "3_3") (pintype "unspecified+no_connect"))
    )
    (net (code "54") (name "unconnected-(MAX98357-Pad4)") (class "Default")
      (node (ref "MAX98357") (pin "4") (pinfunction "4_4") (pintype "unspecified+no_connect"))
    )
    (net (code "55") (name "unconnected-(SCREW6-Pad1)") (class "Default")
      (node (ref "SCREW6") (pin "1") (pinfunction "1_1") (pintype "input+no_connect"))
    )
    (net (code "56") (name "unconnected-(SCREW7-Pad1)") (class "Default")
      (node (ref "SCREW7") (pin "1") (pinfunction "1_1") (pintype "input+no_connect"))
    )
    (net (code "57") (name "unconnected-(SCREW8-Pad1)") (class "Default")
      (node (ref "SCREW8") (pin "1") (pinfunction "1_1") (pintype "input+no_connect"))
    )
    (net (code "58") (name "unconnected-(SCREW9-Pad1)") (class "Default")
      (node (ref "SCREW9") (pin "1") (pinfunction "1_1") (pintype "input+no_connect"))
    )
    (net (code "59") (name "unconnected-(SCREW10-Pad1)") (class "Default")
      (node (ref "SCREW10") (pin "1") (pinfunction "1_1") (pintype "input+no_connect"))
    )
    (net (code "60") (name "unconnected-(SW1-Pad1)") (class "Default")
      (node (ref "SW1") (pin "1") (pinfunction "1_1") (pintype "unspecified+no_connect"))
    )
    (net (code "61") (name "unconnected-(U4-3V3-Pad1)") (class "Default")
      (node (ref "U4") (pin "1") (pinfunction "3V3_1") (pintype "unspecified+no_connect"))
    )
    (net (code "62") (name "unconnected-(U4-MUTE-Pad12)") (class "Default")
      (node (ref "U4") (pin "12") (pinfunction "MUTE_12") (pintype "unspecified+no_connect"))
    )
    (net (code "63") (name "unconnected-(U4-PA0-Pad7)") (class "Default")
      (node (ref "U4") (pin "7") (pinfunction "PA0_7") (pintype "unspecified+no_connect"))
    )
    (net (code "64") (name "unconnected-(U4-PA1-Pad6)") (class "Default")
      (node (ref "U4") (pin "6") (pinfunction "PA1_6") (pintype "unspecified+no_connect"))
    )
    (net (code "65") (name "unconnected-(U4-PA2-Pad5)") (class "Default")
      (node (ref "U4") (pin "5") (pinfunction "PA2_5") (pintype "unspecified+no_connect"))
    )
    (net (code "66") (name "unconnected-(U4-PA3-Pad4)") (class "Default")
      (node (ref "U4") (pin "4") (pinfunction "PA3_4") (pintype "unspecified+no_connect"))
    )
    (net (code "67") (name "unconnected-(U4-PA4-Pad13)") (class "Default")
      (node (ref "U4") (pin "13") (pinfunction "PA4_13") (pintype "unspecified+no_connect"))
    )
    (net (code "68") (name "unconnected-(U4-PA5-Pad3)") (class "Default")
      (node (ref "U4") (pin "3") (pinfunction "PA5_3") (pintype "unspecified+no_connect"))
    )
    (net (code "69") (name "unconnected-(U4-PA6-Pad2)") (class "Default")
      (node (ref "U4") (pin "2") (pinfunction "PA6_2") (pintype "unspecified+no_connect"))
    )
    (net (code "70") (name "unconnected-(U4-PC4-Pad14)") (class "Default")
      (node (ref "U4") (pin "14") (pinfunction "PC4_14") (pintype "unspecified+no_connect"))
    )
  )
)
